# msgeq7-simple.net
KiCad netlist of a schematic drawn in EAGLE
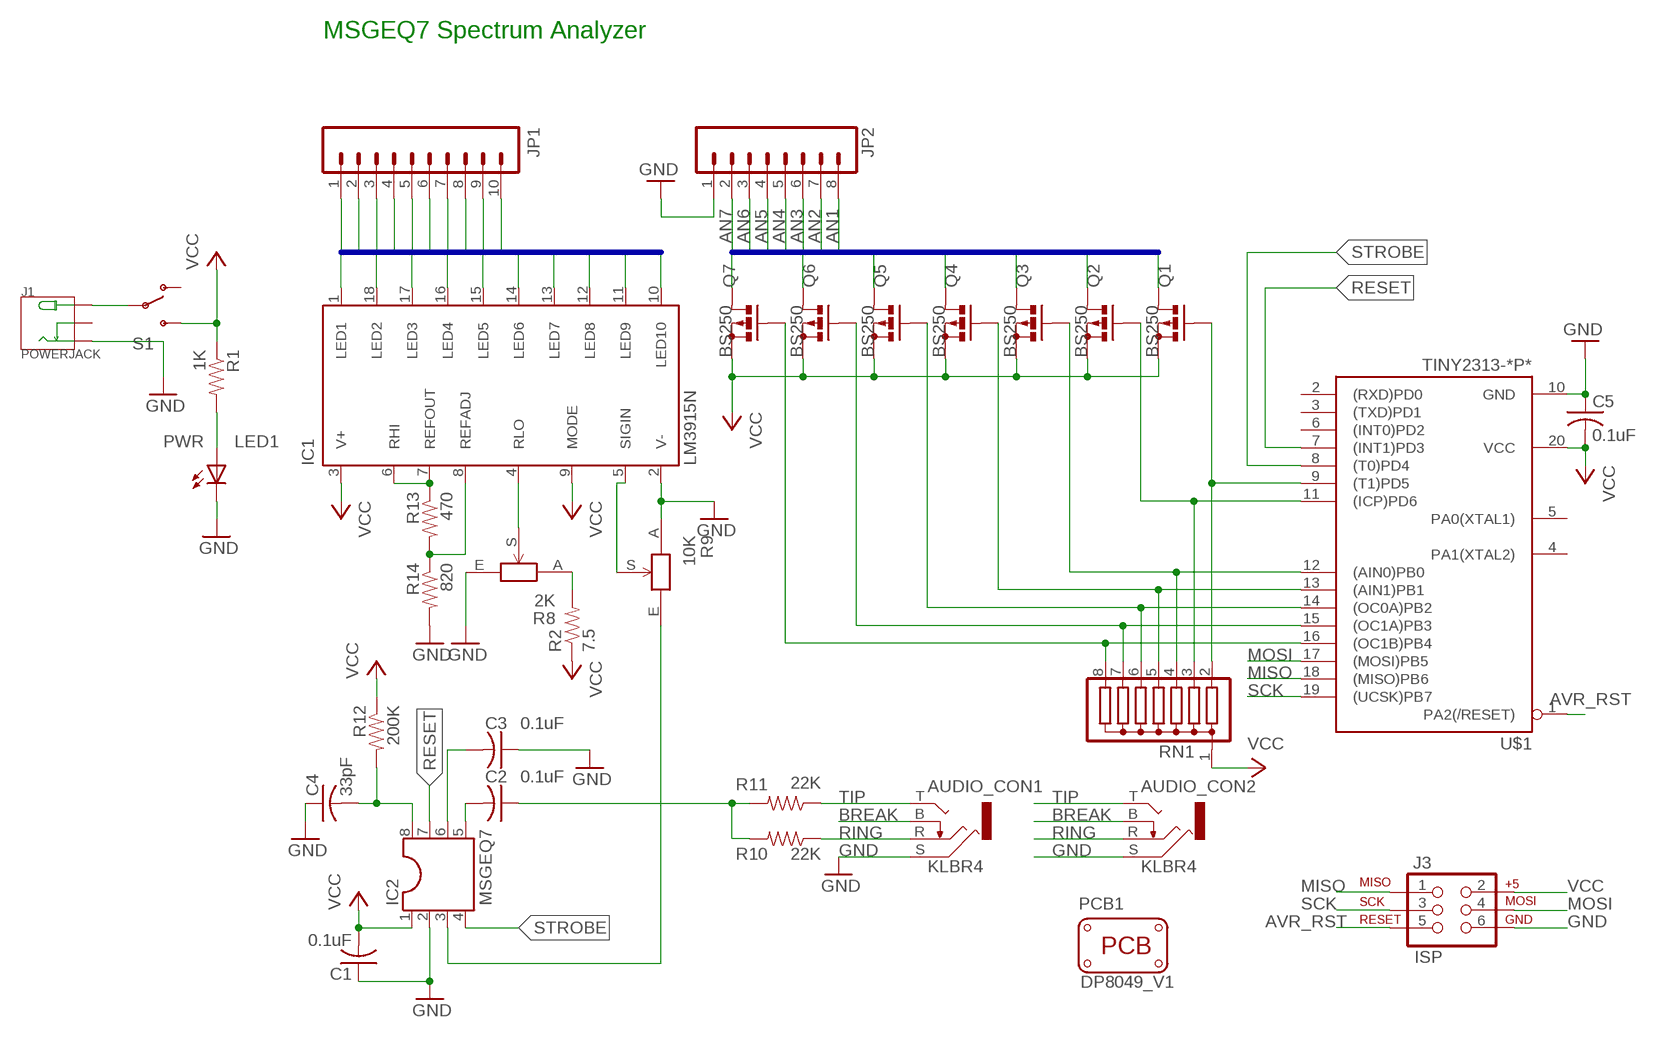
[diagram p0: schematic, sheet 1]

(export (version "E")
  (design (tool "Eeschema 10.0.6"))
  (components
    (comp (ref "AUDIO_CON1")
      (value "KLBR4")
      (footprint "eagle-import:KLBR4")
      (libsource (lib "eagle-import") (part "KLBR4"))
    )
    (comp (ref "AUDIO_CON2")
      (value "KLBR4")
      (footprint "eagle-import:KLBR4")
      (libsource (lib "eagle-import") (part "KLBR4"))
    )
    (comp (ref "C1")
      (value "0.1uF")
      (footprint "eagle-import:C025-025X050")
      (libsource (lib "eagle-import") (part "C-US025-025X050"))
    )
    (comp (ref "C2")
      (value "0.1uF")
      (footprint "eagle-import:C025-025X050")
      (libsource (lib "eagle-import") (part "C-US025-025X050"))
    )
    (comp (ref "C3")
      (value "0.1uF")
      (footprint "eagle-import:C025-025X050")
      (libsource (lib "eagle-import") (part "C-US025-025X050"))
    )
    (comp (ref "C4")
      (value "33pF")
      (footprint "eagle-import:C025-025X050")
      (libsource (lib "eagle-import") (part "C-US025-025X050"))
    )
    (comp (ref "C5")
      (value "0.1uF")
      (footprint "eagle-import:C025-025X050")
      (libsource (lib "eagle-import") (part "C-US025-025X050"))
    )
    (comp (ref "IC1")
      (value "LM3915N")
      (footprint "eagle-import:DIL18")
      (libsource (lib "eagle-import") (part "LM391N5"))
    )
    (comp (ref "IC2")
      (value "MSGEQ7")
      (footprint "eagle-import:DIL08")
      (libsource (lib "eagle-import") (part "DIL8"))
    )
    (comp (ref "J1")
      (value "POWERJACK")
      (footprint "eagle-import:PW-3P-2.1")
      (libsource (lib "eagle-import") (part "JACK-DC-3P-3410020P1"))
    )
    (comp (ref "J3")
      (value "ISP")
      (footprint "eagle-import:2X3")
      (libsource (lib "eagle-import") (part "AVR_SPI_PRG_6PTH"))
    )
    (comp (ref "JP1")
      (value "M10\"")
      (footprint "eagle-import:1X10")
      (libsource (lib "eagle-import") (part "M10{dblquote}"))
    )
    (comp (ref "JP2")
      (value "M081X08")
      (footprint "eagle-import:1X08")
      (libsource (lib "eagle-import") (part "M081X08"))
    )
    (comp (ref "LED1")
      (value "PWR")
      (footprint "eagle-import:LED3MM")
      (libsource (lib "eagle-import") (part "LED3MM"))
    )
    (comp (ref "PCB1")
      (value "PCB_DP_RECTANGLE-80X49")
      (footprint "eagle-import:DP8049_V1")
      (libsource (lib "eagle-import") (part "PCB_DP_RECTANGLE-80X49"))
    )
    (comp (ref "Q1")
      (value "BS250")
      (footprint "eagle-import:TO92-E-LINE")
      (libsource (lib "eagle-import") (part "BS250TO92-E"))
    )
    (comp (ref "Q2")
      (value "BS250")
      (footprint "eagle-import:TO92-E-LINE")
      (libsource (lib "eagle-import") (part "BS250TO92-E"))
    )
    (comp (ref "Q3")
      (value "BS250")
      (footprint "eagle-import:TO92-E-LINE")
      (libsource (lib "eagle-import") (part "BS250TO92-E"))
    )
    (comp (ref "Q4")
      (value "BS250")
      (footprint "eagle-import:TO92-E-LINE")
      (libsource (lib "eagle-import") (part "BS250TO92-E"))
    )
    (comp (ref "Q5")
      (value "BS250")
      (footprint "eagle-import:TO92-E-LINE")
      (libsource (lib "eagle-import") (part "BS250TO92-E"))
    )
    (comp (ref "Q6")
      (value "BS250")
      (footprint "eagle-import:TO92-E-LINE")
      (libsource (lib "eagle-import") (part "BS250TO92-E"))
    )
    (comp (ref "Q7")
      (value "BS250")
      (footprint "eagle-import:TO92-E-LINE")
      (libsource (lib "eagle-import") (part "BS250TO92-E"))
    )
    (comp (ref "R1")
      (value "1K")
      (footprint "eagle-import:AXIAL-0.4")
      (libsource (lib "eagle-import") (part "RESISTORPTH-1/4W"))
    )
    (comp (ref "R2")
      (value "7.5")
      (footprint "eagle-import:AXIAL-0.4")
      (libsource (lib "eagle-import") (part "RESISTORPTH-1/4W"))
    )
    (comp (ref "R8")
      (value "2K")
      (footprint "eagle-import:3352T")
      (libsource (lib "eagle-import") (part "TPOT3352"))
    )
    (comp (ref "R9")
      (value "10K")
      (footprint "eagle-import:3352T")
      (libsource (lib "eagle-import") (part "TPOT3352"))
    )
    (comp (ref "R10")
      (value "22K")
      (footprint "eagle-import:AXIAL-0.4")
      (libsource (lib "eagle-import") (part "RESISTORPTH-1/4W"))
    )
    (comp (ref "R11")
      (value "22K")
      (footprint "eagle-import:AXIAL-0.4")
      (libsource (lib "eagle-import") (part "RESISTORPTH-1/4W"))
    )
    (comp (ref "R12")
      (value "200K")
      (footprint "eagle-import:AXIAL-0.4")
      (libsource (lib "eagle-import") (part "RESISTORPTH-1/4W"))
    )
    (comp (ref "R13")
      (value "470")
      (footprint "eagle-import:AXIAL-0.4")
      (libsource (lib "eagle-import") (part "RESISTORPTH-1/4W"))
    )
    (comp (ref "R14")
      (value "820")
      (footprint "eagle-import:AXIAL-0.4")
      (libsource (lib "eagle-import") (part "RESISTORPTH-1/4W"))
    )
    (comp (ref "RN1")
      (value "G07R")
      (footprint "eagle-import:SIL8")
      (libsource (lib "eagle-import") (part "G07R"))
    )
    (comp (ref "S1")
      (value "SWITCH-SPDTPTH")
      (footprint "eagle-import:SWITCH-SPDT")
      (libsource (lib "eagle-import") (part "SWITCH-SPDTPTH"))
    )
    (comp (ref "U$1")
      (value "TINY2313-*P*")
      (footprint "eagle-import:DIL20")
      (libsource (lib "eagle-import") (part "TINY2313-P"))
    )
  )
  (nets
    (net (code "1") (name "/AN1") (class "Default")
      (node (ref "JP2") (pin "8") (pinfunction "8_8") (pintype "passive"))
      (node (ref "Q1") (pin "D") (pinfunction "D_D") (pintype "passive"))
    )
    (net (code "2") (name "/AN2") (class "Default")
      (node (ref "JP2") (pin "7") (pinfunction "7_7") (pintype "passive"))
      (node (ref "Q2") (pin "D") (pinfunction "D_D") (pintype "passive"))
    )
    (net (code "3") (name "/AN3") (class "Default")
      (node (ref "JP2") (pin "6") (pinfunction "6_6") (pintype "passive"))
      (node (ref "Q3") (pin "D") (pinfunction "D_D") (pintype "passive"))
    )
    (net (code "4") (name "/AN4") (class "Default")
      (node (ref "JP2") (pin "5") (pinfunction "5_5") (pintype "passive"))
      (node (ref "Q4") (pin "D") (pinfunction "D_D") (pintype "passive"))
    )
    (net (code "5") (name "/AN5") (class "Default")
      (node (ref "JP2") (pin "4") (pinfunction "4_4") (pintype "passive"))
      (node (ref "Q5") (pin "D") (pinfunction "D_D") (pintype "passive"))
    )
    (net (code "6") (name "/AN6") (class "Default")
      (node (ref "JP2") (pin "3") (pinfunction "3_3") (pintype "passive"))
      (node (ref "Q6") (pin "D") (pinfunction "D_D") (pintype "passive"))
    )
    (net (code "7") (name "/AN7") (class "Default")
      (node (ref "JP2") (pin "2") (pinfunction "2_2") (pintype "passive"))
      (node (ref "Q7") (pin "D") (pinfunction "D_D") (pintype "passive"))
    )
    (net (code "8") (name "/AVR_RST") (class "Default")
      (node (ref "J3") (pin "5") (pinfunction "5_5") (pintype "passive"))
      (node (ref "U$1") (pin "1") (pinfunction "PA2(/RESET)_1") (pintype "input"))
    )
    (net (code "9") (name "/BREAK") (class "Default")
      (node (ref "AUDIO_CON1") (pin "B") (pinfunction "B_B") (pintype "passive"))
      (node (ref "AUDIO_CON2") (pin "B") (pinfunction "B_B") (pintype "passive"))
    )
    (net (code "10") (name "/CAT1") (class "Default")
      (node (ref "IC1") (pin "1") (pinfunction "LED1_1") (pintype "output"))
      (node (ref "JP1") (pin "1") (pinfunction "1_1") (pintype "passive"))
    )
    (net (code "11") (name "/CAT2") (class "Default")
      (node (ref "IC1") (pin "18") (pinfunction "LED2_18") (pintype "output"))
      (node (ref "JP1") (pin "2") (pinfunction "2_2") (pintype "passive"))
    )
    (net (code "12") (name "/CAT3") (class "Default")
      (node (ref "IC1") (pin "17") (pinfunction "LED3_17") (pintype "output"))
      (node (ref "JP1") (pin "3") (pinfunction "3_3") (pintype "passive"))
    )
    (net (code "13") (name "/CAT4") (class "Default")
      (node (ref "IC1") (pin "16") (pinfunction "LED4_16") (pintype "output"))
      (node (ref "JP1") (pin "4") (pinfunction "4_4") (pintype "passive"))
    )
    (net (code "14") (name "/CAT5") (class "Default")
      (node (ref "IC1") (pin "15") (pinfunction "LED5_15") (pintype "output"))
      (node (ref "JP1") (pin "5") (pinfunction "5_5") (pintype "passive"))
    )
    (net (code "15") (name "/CAT6") (class "Default")
      (node (ref "IC1") (pin "14") (pinfunction "LED6_14") (pintype "output"))
      (node (ref "JP1") (pin "6") (pinfunction "6_6") (pintype "passive"))
    )
    (net (code "16") (name "/CAT7") (class "Default")
      (node (ref "IC1") (pin "13") (pinfunction "LED7_13") (pintype "output"))
      (node (ref "JP1") (pin "7") (pinfunction "7_7") (pintype "passive"))
    )
    (net (code "17") (name "/CAT8") (class "Default")
      (node (ref "IC1") (pin "12") (pinfunction "LED8_12") (pintype "output"))
      (node (ref "JP1") (pin "8") (pinfunction "8_8") (pintype "passive"))
    )
    (net (code "18") (name "/CAT9") (class "Default")
      (node (ref "IC1") (pin "11") (pinfunction "LED9_11") (pintype "output"))
      (node (ref "JP1") (pin "9") (pinfunction "9_9") (pintype "passive"))
    )
    (net (code "19") (name "/CAT10") (class "Default")
      (node (ref "IC1") (pin "10") (pinfunction "LED10_10") (pintype "output"))
      (node (ref "JP1") (pin "10") (pinfunction "10_10") (pintype "passive"))
    )
    (net (code "20") (name "/MISO") (class "Default")
      (node (ref "J3") (pin "1") (pinfunction "1_1") (pintype "passive"))
      (node (ref "U$1") (pin "18") (pinfunction "(MISO)PB6_18") (pintype "bidirectional"))
    )
    (net (code "21") (name "/MOSI") (class "Default")
      (node (ref "J3") (pin "4") (pinfunction "4_4") (pintype "passive"))
      (node (ref "U$1") (pin "17") (pinfunction "(MOSI)PB5_17") (pintype "bidirectional"))
    )
    (net (code "22") (name "/RING") (class "Default")
      (node (ref "AUDIO_CON1") (pin "R") (pinfunction "R_R") (pintype "passive"))
      (node (ref "AUDIO_CON2") (pin "R") (pinfunction "R_R") (pintype "passive"))
      (node (ref "R10") (pin "P$1") (pinfunction "1_P$1") (pintype "passive"))
    )
    (net (code "23") (name "/SCK") (class "Default")
      (node (ref "J3") (pin "3") (pinfunction "3_3") (pintype "passive"))
      (node (ref "U$1") (pin "19") (pinfunction "(UCSK)PB7_19") (pintype "bidirectional"))
    )
    (net (code "24") (name "/TIP") (class "Default")
      (node (ref "AUDIO_CON1") (pin "T") (pinfunction "T_T") (pintype "passive"))
      (node (ref "AUDIO_CON2") (pin "T") (pinfunction "T_T") (pintype "passive"))
      (node (ref "R11") (pin "P$1") (pinfunction "1_P$1") (pintype "passive"))
    )
    (net (code "25") (name "GND") (class "Default")
      (node (ref "AUDIO_CON1") (pin "S") (pinfunction "S_S") (pintype "passive"))
      (node (ref "AUDIO_CON2") (pin "S") (pinfunction "S_S") (pintype "passive"))
      (node (ref "C1") (pin "1") (pinfunction "1_1") (pintype "passive"))
      (node (ref "C3") (pin "1") (pinfunction "1_1") (pintype "passive"))
      (node (ref "C4") (pin "1") (pinfunction "1_1") (pintype "passive"))
      (node (ref "C5") (pin "1") (pinfunction "1_1") (pintype "passive"))
      (node (ref "IC1") (pin "2") (pinfunction "V-_2") (pintype "power_in"))
      (node (ref "IC2") (pin "2") (pinfunction "2_2") (pintype "passive"))
      (node (ref "J1") (pin "-1") (pinfunction "-_-1") (pintype "bidirectional"))
      (node (ref "J3") (pin "6") (pinfunction "6_6") (pintype "passive"))
      (node (ref "JP2") (pin "1") (pinfunction "1_1") (pintype "passive"))
      (node (ref "LED1") (pin "K") (pinfunction "C_K") (pintype "passive"))
      (node (ref "R14") (pin "P$2") (pinfunction "2_P$2") (pintype "passive"))
      (node (ref "R8") (pin "E") (pinfunction "E_E") (pintype "passive"))
      (node (ref "R9") (pin "A") (pinfunction "A_A") (pintype "passive"))
      (node (ref "U$1") (pin "10") (pinfunction "GND_10") (pintype "power_in"))
    )
    (net (code "26") (name "Net-(C2-Pad2)") (class "Default")
      (node (ref "C2") (pin "2") (pinfunction "2_2") (pintype "passive"))
      (node (ref "IC2") (pin "5") (pinfunction "5_5") (pintype "passive"))
    )
    (net (code "27") (name "Net-(C3-Pad2)") (class "Default")
      (node (ref "C3") (pin "2") (pinfunction "2_2") (pintype "passive"))
      (node (ref "IC2") (pin "6") (pinfunction "6_6") (pintype "passive"))
    )
    (net (code "28") (name "Net-(IC1-REFADJ)") (class "Default")
      (node (ref "IC1") (pin "8") (pinfunction "REFADJ_8") (pintype "passive"))
      (node (ref "R13") (pin "P$2") (pinfunction "2_P$2") (pintype "passive"))
      (node (ref "R14") (pin "P$1") (pinfunction "1_P$1") (pintype "passive"))
    )
    (net (code "29") (name "Net-(IC1-REFOUT)") (class "Default")
      (node (ref "IC1") (pin "6") (pinfunction "RHI_6") (pintype "input"))
      (node (ref "IC1") (pin "7") (pinfunction "REFOUT_7") (pintype "output"))
      (node (ref "R13") (pin "P$1") (pinfunction "1_P$1") (pintype "passive"))
    )
    (net (code "30") (name "Net-(IC1-RLO)") (class "Default")
      (node (ref "IC1") (pin "4") (pinfunction "RLO_4") (pintype "input"))
      (node (ref "R8") (pin "S") (pinfunction "S_S") (pintype "passive"))
    )
    (net (code "31") (name "Net-(IC1-SIGIN)") (class "Default")
      (node (ref "IC1") (pin "5") (pinfunction "SIGIN_5") (pintype "input"))
      (node (ref "R9") (pin "S") (pinfunction "S_S") (pintype "passive"))
    )
    (net (code "32") (name "Net-(IC2-Pad3)") (class "Default")
      (node (ref "IC2") (pin "3") (pinfunction "3_3") (pintype "passive"))
      (node (ref "R9") (pin "E") (pinfunction "E_E") (pintype "passive"))
    )
    (net (code "33") (name "Net-(R1-2)") (class "Default")
      (node (ref "LED1") (pin "A") (pinfunction "A_A") (pintype "passive"))
      (node (ref "R1") (pin "P$2") (pinfunction "2_P$2") (pintype "passive"))
    )
    (net (code "34") (name "Net-(R2-2)") (class "Default")
      (node (ref "R2") (pin "P$2") (pinfunction "2_P$2") (pintype "passive"))
      (node (ref "R8") (pin "A") (pinfunction "A_A") (pintype "passive"))
    )
    (net (code "35") (name "Net-(R10-2)") (class "Default")
      (node (ref "C2") (pin "1") (pinfunction "1_1") (pintype "passive"))
      (node (ref "R10") (pin "P$2") (pinfunction "2_P$2") (pintype "passive"))
      (node (ref "R11") (pin "P$2") (pinfunction "2_P$2") (pintype "passive"))
    )
    (net (code "36") (name "Net-(R12-2)") (class "Default")
      (node (ref "C4") (pin "2") (pinfunction "2_2") (pintype "passive"))
      (node (ref "IC2") (pin "8") (pinfunction "8_8") (pintype "passive"))
      (node (ref "R12") (pin "P$2") (pinfunction "2_P$2") (pintype "passive"))
    )
    (net (code "37") (name "Net-(S1-P)") (class "Default")
      (node (ref "J1") (pin "+") (pinfunction "+_+") (pintype "bidirectional"))
      (node (ref "S1") (pin "2") (pinfunction "P_2") (pintype "passive"))
    )
    (net (code "38") (name "Net-(U$1-(AIN0)PB0)") (class "Default")
      (node (ref "Q3") (pin "G") (pinfunction "G_G") (pintype "passive"))
      (node (ref "RN1") (pin "4") (pinfunction "4_4") (pintype "passive"))
      (node (ref "U$1") (pin "12") (pinfunction "(AIN0)PB0_12") (pintype "bidirectional"))
    )
    (net (code "39") (name "Net-(U$1-(AIN1)PB1)") (class "Default")
      (node (ref "Q4") (pin "G") (pinfunction "G_G") (pintype "passive"))
      (node (ref "RN1") (pin "5") (pinfunction "5_5") (pintype "passive"))
      (node (ref "U$1") (pin "13") (pinfunction "(AIN1)PB1_13") (pintype "bidirectional"))
    )
    (net (code "40") (name "Net-(U$1-(ICP)PD6)") (class "Default")
      (node (ref "Q2") (pin "G") (pinfunction "G_G") (pintype "passive"))
      (node (ref "RN1") (pin "3") (pinfunction "3_3") (pintype "passive"))
      (node (ref "U$1") (pin "11") (pinfunction "(ICP)PD6_11") (pintype "bidirectional"))
    )
    (net (code "41") (name "Net-(U$1-(OC0A)PB2)") (class "Default")
      (node (ref "Q5") (pin "G") (pinfunction "G_G") (pintype "passive"))
      (node (ref "RN1") (pin "6") (pinfunction "6_6") (pintype "passive"))
      (node (ref "U$1") (pin "14") (pinfunction "(OC0A)PB2_14") (pintype "bidirectional"))
    )
    (net (code "42") (name "Net-(U$1-(OC1A)PB3)") (class "Default")
      (node (ref "Q6") (pin "G") (pinfunction "G_G") (pintype "passive"))
      (node (ref "RN1") (pin "7") (pinfunction "7_7") (pintype "passive"))
      (node (ref "U$1") (pin "15") (pinfunction "(OC1A)PB3_15") (pintype "bidirectional"))
    )
    (net (code "43") (name "Net-(U$1-(OC1B)PB4)") (class "Default")
      (node (ref "Q7") (pin "G") (pinfunction "G_G") (pintype "passive"))
      (node (ref "RN1") (pin "8") (pinfunction "8_8") (pintype "passive"))
      (node (ref "U$1") (pin "16") (pinfunction "(OC1B)PB4_16") (pintype "bidirectional"))
    )
    (net (code "44") (name "Net-(U$1-(T1)PD5)") (class "Default")
      (node (ref "Q1") (pin "G") (pinfunction "G_G") (pintype "passive"))
      (node (ref "RN1") (pin "2") (pinfunction "2_2") (pintype "passive"))
      (node (ref "U$1") (pin "9") (pinfunction "(T1)PD5_9") (pintype "bidirectional"))
    )
    (net (code "45") (name "RESET") (class "Default")
      (node (ref "IC2") (pin "7") (pinfunction "7_7") (pintype "passive"))
      (node (ref "U$1") (pin "7") (pinfunction "(INT1)PD3_7") (pintype "bidirectional"))
    )
    (net (code "46") (name "STROBE") (class "Default")
      (node (ref "IC2") (pin "4") (pinfunction "4_4") (pintype "passive"))
      (node (ref "U$1") (pin "8") (pinfunction "(T0)PD4_8") (pintype "bidirectional"))
    )
    (net (code "47") (name "VCC") (class "Default")
      (node (ref "C1") (pin "2") (pinfunction "2_2") (pintype "passive"))
      (node (ref "C5") (pin "2") (pinfunction "2_2") (pintype "passive"))
      (node (ref "IC1") (pin "3") (pinfunction "V+_3") (pintype "power_in"))
      (node (ref "IC1") (pin "9") (pinfunction "MODE_9") (pintype "input"))
      (node (ref "IC2") (pin "1") (pinfunction "1_1") (pintype "passive"))
      (node (ref "J3") (pin "2") (pinfunction "2_2") (pintype "passive"))
      (node (ref "Q1") (pin "S") (pinfunction "S_S") (pintype "passive"))
      (node (ref "Q2") (pin "S") (pinfunction "S_S") (pintype "passive"))
      (node (ref "Q3") (pin "S") (pinfunction "S_S") (pintype "passive"))
      (node (ref "Q4") (pin "S") (pinfunction "S_S") (pintype "passive"))
      (node (ref "Q5") (pin "S") (pinfunction "S_S") (pintype "passive"))
      (node (ref "Q6") (pin "S") (pinfunction "S_S") (pintype "passive"))
      (node (ref "Q7") (pin "S") (pinfunction "S_S") (pintype "passive"))
      (node (ref "R1") (pin "P$1") (pinfunction "1_P$1") (pintype "passive"))
      (node (ref "R12") (pin "P$1") (pinfunction "1_P$1") (pintype "passive"))
      (node (ref "R2") (pin "P$1") (pinfunction "1_P$1") (pintype "passive"))
      (node (ref "RN1") (pin "1") (pinfunction "1_1") (pintype "passive"))
      (node (ref "S1") (pin "3") (pinfunction "S_3") (pintype "passive"))
      (node (ref "U$1") (pin "20") (pinfunction "VCC_20") (pintype "power_in"))
    )
    (net (code "48") (name "unconnected-(J1-CDN-Pad-2)") (class "Default")
      (node (ref "J1") (pin "-2") (pinfunction "CDN_-2") (pintype "bidirectional"))
    )
    (net (code "49") (name "unconnected-(S1-O-Pad1)") (class "Default")
      (node (ref "S1") (pin "1") (pinfunction "O_1") (pintype "passive"))
    )
    (net (code "50") (name "unconnected-(U$1-(INT0)PD2-Pad6)") (class "Default")
      (node (ref "U$1") (pin "6") (pinfunction "(INT0)PD2_6") (pintype "bidirectional"))
    )
    (net (code "51") (name "unconnected-(U$1-(RXD)PD0-Pad2)") (class "Default")
      (node (ref "U$1") (pin "2") (pinfunction "(RXD)PD0_2") (pintype "bidirectional"))
    )
    (net (code "52") (name "unconnected-(U$1-(TXD)PD1-Pad3)") (class "Default")
      (node (ref "U$1") (pin "3") (pinfunction "(TXD)PD1_3") (pintype "bidirectional"))
    )
    (net (code "53") (name "unconnected-(U$1-PA0(XTAL1)-Pad5)") (class "Default")
      (node (ref "U$1") (pin "5") (pinfunction "PA0(XTAL1)_5") (pintype "bidirectional"))
    )
    (net (code "54") (name "unconnected-(U$1-PA1(XTAL2)-Pad4)") (class "Default")
      (node (ref "U$1") (pin "4") (pinfunction "PA1(XTAL2)_4") (pintype "bidirectional"))
    )
  )
)
